# H-00488_-_Connectors_Downstream.net
KiCad netlist of a schematic drawn in Altium Designer
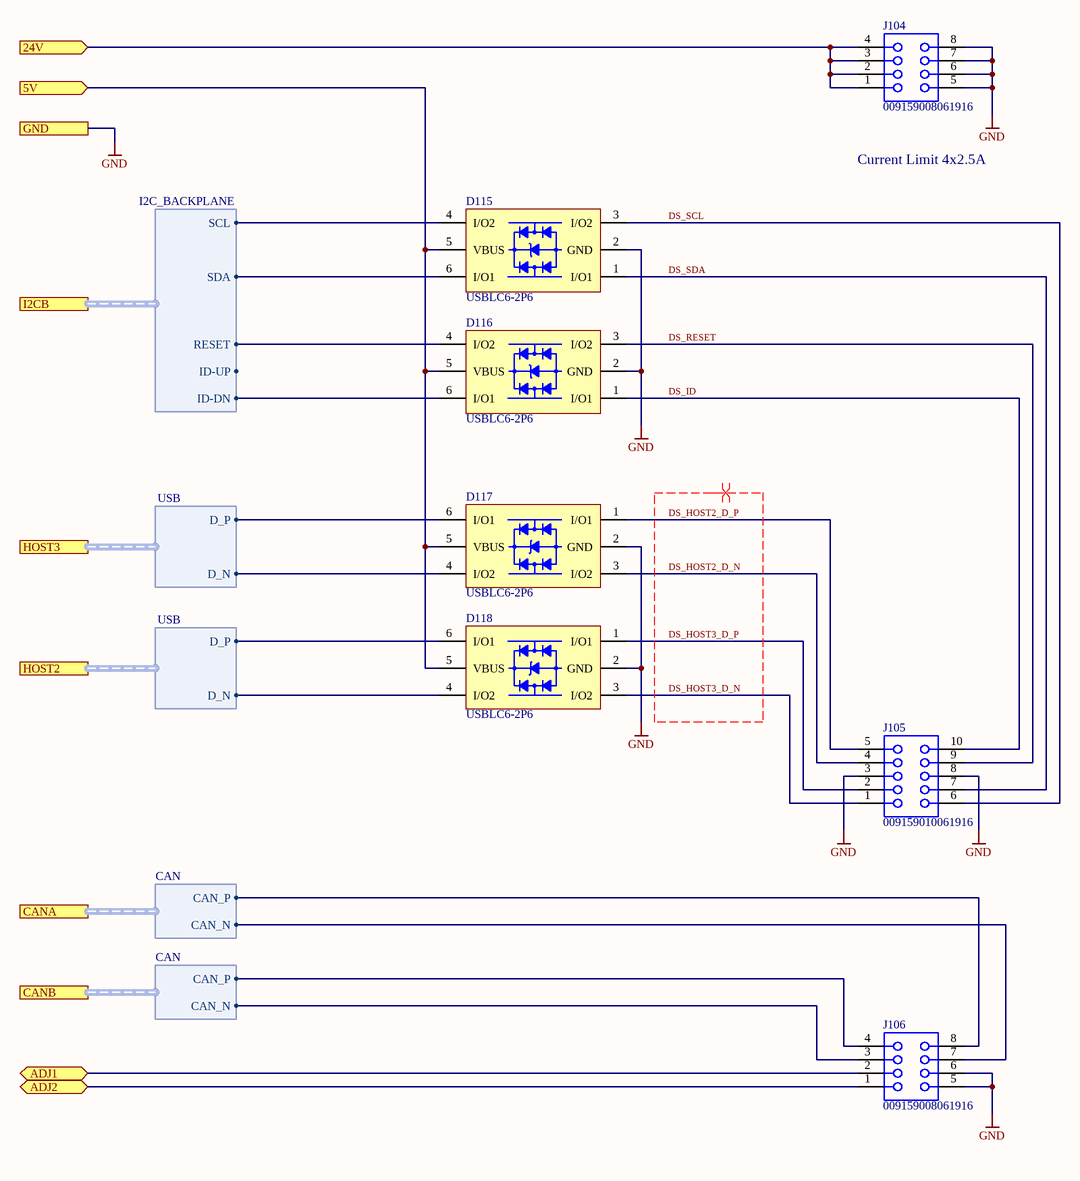
[diagram p0: H-00488 - Connectors Downstream.SchDoc]

(export (version "E")
  (design (tool "Eeschema 10.0.6"))
  (components
    (comp (ref "D115")
      (value "USBLC6-2P6")
      (footprint "DIOSOFL6P50_160X160X95L29X26")
      (description "TVS DIODE 5.25VWM 17VC SOT666")
      (libsource (lib "Hiber") (part "ST_USBLC6-2"))
    )
    (comp (ref "D116")
      (value "USBLC6-2P6")
      (footprint "DIOSOFL6P50_160X160X95L29X26")
      (description "TVS DIODE 5.25VWM 17VC SOT666")
      (libsource (lib "Hiber") (part "ST_USBLC6-2"))
    )
    (comp (ref "D117")
      (value "USBLC6-2P6")
      (footprint "DIOSOFL6P50_160X160X95L29X26")
      (description "TVS DIODE 5.25VWM 17VC SOT666")
      (libsource (lib "") (part "ST_USBLC6-2_1"))
    )
    (comp (ref "D118")
      (value "USBLC6-2P6")
      (footprint "DIOSOFL6P50_160X160X95L29X26")
      (description "TVS DIODE 5.25VWM 17VC SOT666")
      (libsource (lib "") (part "ST_USBLC6-2_1"))
    )
    (comp (ref "J104")
      (value "009159008061916")
      (footprint "AVX_00-9159-008")
      (description "CONN SSL BRIDGE 8POS 2MM")
      (libsource (lib "Hiber") (part "HEADER-FEMALE-02X04-N"))
    )
    (comp (ref "J105")
      (value "009159010061916")
      (footprint "AVX_00-9159-010")
      (description "AVX INTERCONNECT - 009159010061916 - CARD EDGE CONN, DUAL SIDE, 10POS, SMD")
      (libsource (lib "Hiber") (part "HEADER-FEMALE-02X05-N"))
    )
    (comp (ref "J106")
      (value "009159008061916")
      (footprint "AVX_00-9159-008")
      (description "CONN SSL BRIDGE 8POS 2MM")
      (libsource (lib "Hiber") (part "HEADER-FEMALE-02X04-N"))
    )
  )
  (nets
    (net (code "4") (name "/5V") (class "Default")
      (node (ref "D115") (pin "5") (pinfunction "VBUS_5") (pintype "passive"))
      (node (ref "D116") (pin "5") (pinfunction "VBUS_5") (pintype "passive"))
      (node (ref "D117") (pin "5") (pinfunction "VBUS_5") (pintype "passive"))
      (node (ref "D118") (pin "5") (pinfunction "VBUS_5") (pintype "passive"))
    )
    (net (code "5") (name "/24V") (class "Default")
      (node (ref "J104") (pin "1") (pinfunction "1_1") (pintype "passive"))
      (node (ref "J104") (pin "2") (pinfunction "2_2") (pintype "passive"))
      (node (ref "J104") (pin "3") (pinfunction "3_3") (pintype "passive"))
      (node (ref "J104") (pin "4") (pinfunction "4_4") (pintype "passive"))
    )
    (net (code "6") (name "/ADJ1") (class "Default")
      (node (ref "J106") (pin "2") (pinfunction "2_2") (pintype "passive"))
    )
    (net (code "7") (name "/ADJ2") (class "Default")
      (node (ref "J106") (pin "1") (pinfunction "1_1") (pintype "passive"))
    )
    (net (code "8") (name "/DS_HOST2_D_N") (class "Default")
      (node (ref "D117") (pin "3") (pinfunction "I/O2_3") (pintype "passive"))
      (node (ref "J105") (pin "4") (pinfunction "4_4") (pintype "passive"))
    )
    (net (code "9") (name "/DS_HOST2_D_P") (class "Default")
      (node (ref "D117") (pin "1") (pinfunction "I/O1_1") (pintype "passive"))
      (node (ref "J105") (pin "5") (pinfunction "5_5") (pintype "passive"))
    )
    (net (code "10") (name "/DS_HOST3_D_N") (class "Default")
      (node (ref "D118") (pin "3") (pinfunction "I/O2_3") (pintype "passive"))
      (node (ref "J105") (pin "1") (pinfunction "1_1") (pintype "passive"))
    )
    (net (code "11") (name "/DS_HOST3_D_P") (class "Default")
      (node (ref "D118") (pin "1") (pinfunction "I/O1_1") (pintype "passive"))
      (node (ref "J105") (pin "2") (pinfunction "2_2") (pintype "passive"))
    )
    (net (code "12") (name "/DS_ID") (class "Default")
      (node (ref "D116") (pin "1") (pinfunction "I/O1_1") (pintype "passive"))
      (node (ref "J105") (pin "10") (pinfunction "10_10") (pintype "passive"))
    )
    (net (code "13") (name "/DS_RESET") (class "Default")
      (node (ref "D116") (pin "3") (pinfunction "I/O2_3") (pintype "passive"))
      (node (ref "J105") (pin "9") (pinfunction "9_9") (pintype "passive"))
    )
    (net (code "14") (name "/DS_SCL") (class "Default")
      (node (ref "D115") (pin "3") (pinfunction "I/O2_3") (pintype "passive"))
      (node (ref "J105") (pin "6") (pinfunction "6_6") (pintype "passive"))
    )
    (net (code "15") (name "/DS_SDA") (class "Default")
      (node (ref "D115") (pin "1") (pinfunction "I/O1_1") (pintype "passive"))
      (node (ref "J105") (pin "7") (pinfunction "7_7") (pintype "passive"))
    )
    (net (code "16") (name "/ID-DN") (class "Default")
      (node (ref "D116") (pin "6") (pinfunction "I/O1_6") (pintype "passive"))
    )
    (net (code "17") (name "/RESET") (class "Default")
      (node (ref "D116") (pin "4") (pinfunction "I/O2_4") (pintype "passive"))
    )
    (net (code "18") (name "/SCL") (class "Default")
      (node (ref "D115") (pin "4") (pinfunction "I/O2_4") (pintype "passive"))
    )
    (net (code "19") (name "/SDA") (class "Default")
      (node (ref "D115") (pin "6") (pinfunction "I/O1_6") (pintype "passive"))
    )
    (net (code "23") (name "GND") (class "Default")
      (node (ref "D115") (pin "2") (pinfunction "GND_2") (pintype "passive"))
      (node (ref "D116") (pin "2") (pinfunction "GND_2") (pintype "passive"))
      (node (ref "D117") (pin "2") (pinfunction "GND_2") (pintype "passive"))
      (node (ref "D118") (pin "2") (pinfunction "GND_2") (pintype "passive"))
      (node (ref "J104") (pin "5") (pinfunction "5_5") (pintype "passive"))
      (node (ref "J104") (pin "6") (pinfunction "6_6") (pintype "passive"))
      (node (ref "J104") (pin "7") (pinfunction "7_7") (pintype "passive"))
      (node (ref "J104") (pin "8") (pinfunction "8_8") (pintype "passive"))
      (node (ref "J105") (pin "3") (pinfunction "3_3") (pintype "passive"))
      (node (ref "J105") (pin "8") (pinfunction "8_8") (pintype "passive"))
      (node (ref "J106") (pin "5") (pinfunction "5_5") (pintype "passive"))
      (node (ref "J106") (pin "6") (pinfunction "6_6") (pintype "passive"))
    )
    (net (code "24") (name "unconnected-(D117-I{slash}O1-Pad6)") (class "Default")
      (node (ref "D117") (pin "6") (pinfunction "I/O1_6") (pintype "passive"))
    )
    (net (code "25") (name "unconnected-(D117-I{slash}O2-Pad4)") (class "Default")
      (node (ref "D117") (pin "4") (pinfunction "I/O2_4") (pintype "passive"))
    )
    (net (code "26") (name "unconnected-(D118-I{slash}O1-Pad6)") (class "Default")
      (node (ref "D118") (pin "6") (pinfunction "I/O1_6") (pintype "passive"))
    )
    (net (code "27") (name "unconnected-(D118-I{slash}O2-Pad4)") (class "Default")
      (node (ref "D118") (pin "4") (pinfunction "I/O2_4") (pintype "passive"))
    )
    (net (code "28") (name "unconnected-(J106-Pad3)") (class "Default")
      (node (ref "J106") (pin "3") (pinfunction "3_3") (pintype "passive"))
    )
    (net (code "29") (name "unconnected-(J106-Pad4)") (class "Default")
      (node (ref "J106") (pin "4") (pinfunction "4_4") (pintype "passive"))
    )
    (net (code "30") (name "unconnected-(J106-Pad7)") (class "Default")
      (node (ref "J106") (pin "7") (pinfunction "7_7") (pintype "passive"))
    )
    (net (code "31") (name "unconnected-(J106-Pad8)") (class "Default")
      (node (ref "J106") (pin "8") (pinfunction "8_8") (pintype "passive"))
    )
  )
)
